# CatFeeder-Drive.net
KiCad netlist of a schematic drawn in EAGLE
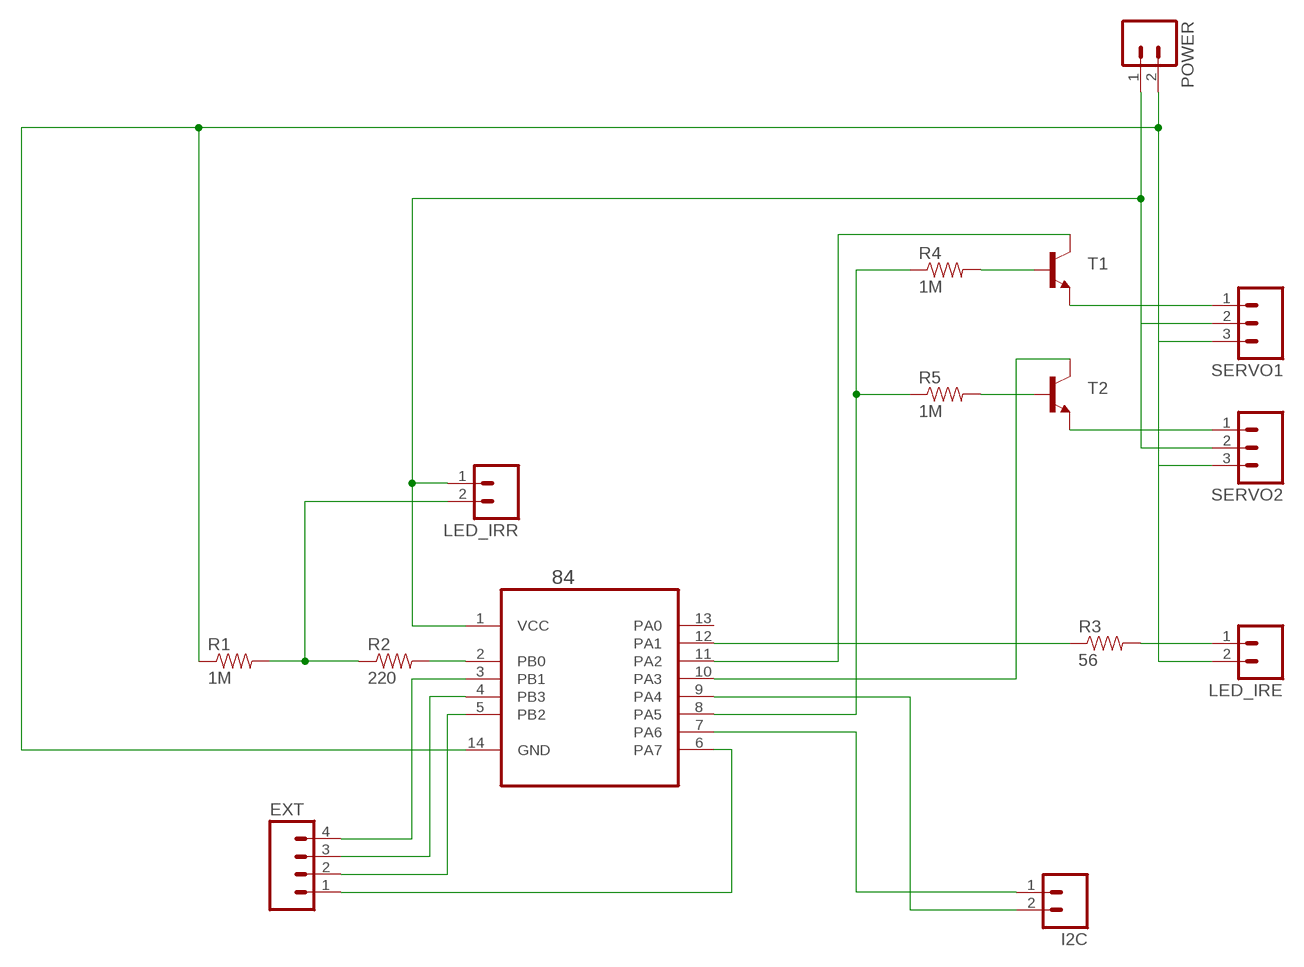
[diagram p0: schematic, sheet 1]

(export (version "E")
  (design (tool "Eeschema 10.0.6"))
  (components
    (comp (ref "84")
      (value "ATTINY84-20PU")
      (footprint "eagle-import:DIP254P762X533-14")
      (libsource (lib "eagle-import") (part "ATTINY84-20PU"))
    )
    (comp (ref "EXT")
      (value "M041X04_NO_SILK")
      (footprint "eagle-import:1X04_NO_SILK")
      (libsource (lib "eagle-import") (part "M041X04_NO_SILK"))
    )
    (comp (ref "I2C")
      (value "M02PTH")
      (footprint "eagle-import:1X02")
      (libsource (lib "eagle-import") (part "M02PTH"))
    )
    (comp (ref "LED_IRE")
      (value "M02LOCK")
      (footprint "eagle-import:1X02_LOCK")
      (libsource (lib "eagle-import") (part "M02LOCK"))
    )
    (comp (ref "LED_IRR")
      (value "M02LOCK")
      (footprint "eagle-import:1X02_LOCK")
      (libsource (lib "eagle-import") (part "M02LOCK"))
    )
    (comp (ref "POWER")
      (value "M02LOCK")
      (footprint "eagle-import:1X02_LOCK")
      (libsource (lib "eagle-import") (part "M02LOCK"))
    )
    (comp (ref "R1")
      (value "1M")
      (footprint "eagle-import:AXIAL-0.4")
      (libsource (lib "eagle-import") (part "RESISTORPTH-1/4W"))
    )
    (comp (ref "R2")
      (value "220")
      (footprint "eagle-import:AXIAL-0.4")
      (libsource (lib "eagle-import") (part "RESISTORPTH-1/4W"))
    )
    (comp (ref "R3")
      (value "56")
      (footprint "eagle-import:AXIAL-0.4")
      (libsource (lib "eagle-import") (part "RESISTORPTH-1/4W"))
    )
    (comp (ref "R4")
      (value "1M")
      (footprint "eagle-import:AXIAL-0.4")
      (libsource (lib "eagle-import") (part "RESISTORPTH-1/4W"))
    )
    (comp (ref "R5")
      (value "1M")
      (footprint "eagle-import:AXIAL-0.4")
      (libsource (lib "eagle-import") (part "RESISTORPTH-1/4W"))
    )
    (comp (ref "SERVO1")
      (value "M031X03_NO_SILK")
      (footprint "eagle-import:1X03_NO_SILK")
      (libsource (lib "eagle-import") (part "M031X03_NO_SILK"))
    )
    (comp (ref "SERVO2")
      (value "M031X03_NO_SILK")
      (footprint "eagle-import:1X03_NO_SILK")
      (libsource (lib "eagle-import") (part "M031X03_NO_SILK"))
    )
    (comp (ref "T1")
      (value "TRANSISTOR_NPNBC547")
      (footprint "eagle-import:TO-92-AMMO")
      (libsource (lib "eagle-import") (part "TRANSISTOR_NPNBC547"))
    )
    (comp (ref "T2")
      (value "TRANSISTOR_NPNBC547")
      (footprint "eagle-import:TO-92-AMMO")
      (libsource (lib "eagle-import") (part "TRANSISTOR_NPNBC547"))
    )
  )
  (nets
    (net (code "1") (name "Net-(84-GND)") (class "Default")
      (node (ref "84") (pin "14") (pinfunction "GND_14") (pintype "passive"))
      (node (ref "LED_IRE") (pin "2") (pinfunction "2_2") (pintype "passive"))
      (node (ref "POWER") (pin "2") (pinfunction "2_2") (pintype "passive"))
      (node (ref "R1") (pin "P$1") (pinfunction "1_P$1") (pintype "passive"))
      (node (ref "SERVO1") (pin "3") (pinfunction "3_3") (pintype "passive"))
      (node (ref "SERVO2") (pin "3") (pinfunction "3_3") (pintype "passive"))
    )
    (net (code "2") (name "Net-(84-PA1)") (class "Default")
      (node (ref "84") (pin "12") (pinfunction "PA1_12") (pintype "bidirectional"))
      (node (ref "R3") (pin "P$1") (pinfunction "1_P$1") (pintype "passive"))
    )
    (net (code "3") (name "Net-(84-PA2)") (class "Default")
      (node (ref "84") (pin "11") (pinfunction "PA2_11") (pintype "bidirectional"))
      (node (ref "T1") (pin "1") (pinfunction "C_1") (pintype "passive"))
    )
    (net (code "4") (name "Net-(84-PA3)") (class "Default")
      (node (ref "84") (pin "10") (pinfunction "PA3_10") (pintype "bidirectional"))
      (node (ref "T2") (pin "1") (pinfunction "C_1") (pintype "passive"))
    )
    (net (code "5") (name "Net-(84-PA4)") (class "Default")
      (node (ref "84") (pin "9") (pinfunction "PA4_9") (pintype "bidirectional"))
      (node (ref "I2C") (pin "2") (pinfunction "2_2") (pintype "passive"))
    )
    (net (code "6") (name "Net-(84-PA5)") (class "Default")
      (node (ref "84") (pin "8") (pinfunction "PA5_8") (pintype "bidirectional"))
      (node (ref "R4") (pin "P$1") (pinfunction "1_P$1") (pintype "passive"))
      (node (ref "R5") (pin "P$1") (pinfunction "1_P$1") (pintype "passive"))
    )
    (net (code "7") (name "Net-(84-PA6)") (class "Default")
      (node (ref "84") (pin "7") (pinfunction "PA6_7") (pintype "bidirectional"))
      (node (ref "I2C") (pin "1") (pinfunction "1_1") (pintype "passive"))
    )
    (net (code "8") (name "Net-(84-PA7)") (class "Default")
      (node (ref "84") (pin "6") (pinfunction "PA7_6") (pintype "bidirectional"))
      (node (ref "EXT") (pin "1") (pinfunction "1_1") (pintype "passive"))
    )
    (net (code "9") (name "Net-(84-PB0)") (class "Default")
      (node (ref "84") (pin "2") (pinfunction "PB0_2") (pintype "bidirectional"))
      (node (ref "R2") (pin "P$2") (pinfunction "2_P$2") (pintype "passive"))
    )
    (net (code "10") (name "Net-(84-PB1)") (class "Default")
      (node (ref "84") (pin "3") (pinfunction "PB1_3") (pintype "bidirectional"))
      (node (ref "EXT") (pin "4") (pinfunction "4_4") (pintype "passive"))
    )
    (net (code "11") (name "Net-(84-PB2)") (class "Default")
      (node (ref "84") (pin "5") (pinfunction "PB2_5") (pintype "bidirectional"))
      (node (ref "EXT") (pin "2") (pinfunction "2_2") (pintype "passive"))
    )
    (net (code "12") (name "Net-(84-PB3)") (class "Default")
      (node (ref "84") (pin "4") (pinfunction "PB3_4") (pintype "bidirectional"))
      (node (ref "EXT") (pin "3") (pinfunction "3_3") (pintype "passive"))
    )
    (net (code "13") (name "Net-(84-VCC)") (class "Default")
      (node (ref "84") (pin "1") (pinfunction "VCC_1") (pintype "power_in"))
      (node (ref "LED_IRR") (pin "1") (pinfunction "1_1") (pintype "passive"))
      (node (ref "POWER") (pin "1") (pinfunction "1_1") (pintype "passive"))
      (node (ref "SERVO1") (pin "2") (pinfunction "2_2") (pintype "passive"))
      (node (ref "SERVO2") (pin "2") (pinfunction "2_2") (pintype "passive"))
    )
    (net (code "14") (name "Net-(R1-2)") (class "Default")
      (node (ref "LED_IRR") (pin "2") (pinfunction "2_2") (pintype "passive"))
      (node (ref "R1") (pin "P$2") (pinfunction "2_P$2") (pintype "passive"))
      (node (ref "R2") (pin "P$1") (pinfunction "1_P$1") (pintype "passive"))
    )
    (net (code "15") (name "Net-(R3-2)") (class "Default")
      (node (ref "LED_IRE") (pin "1") (pinfunction "1_1") (pintype "passive"))
      (node (ref "R3") (pin "P$2") (pinfunction "2_P$2") (pintype "passive"))
    )
    (net (code "16") (name "Net-(R4-2)") (class "Default")
      (node (ref "R4") (pin "P$2") (pinfunction "2_P$2") (pintype "passive"))
      (node (ref "T1") (pin "2") (pinfunction "B_2") (pintype "passive"))
    )
    (net (code "17") (name "Net-(R5-2)") (class "Default")
      (node (ref "R5") (pin "P$2") (pinfunction "2_P$2") (pintype "passive"))
      (node (ref "T2") (pin "2") (pinfunction "B_2") (pintype "passive"))
    )
    (net (code "18") (name "Net-(T1-E)") (class "Default")
      (node (ref "SERVO1") (pin "1") (pinfunction "1_1") (pintype "passive"))
      (node (ref "T1") (pin "3") (pinfunction "E_3") (pintype "passive"))
    )
    (net (code "19") (name "Net-(T2-E)") (class "Default")
      (node (ref "SERVO2") (pin "1") (pinfunction "1_1") (pintype "passive"))
      (node (ref "T2") (pin "3") (pinfunction "E_3") (pintype "passive"))
    )
    (net (code "20") (name "unconnected-(84-PA0-Pad13)") (class "Default")
      (node (ref "84") (pin "13") (pinfunction "PA0_13") (pintype "bidirectional"))
    )
  )
)
